# PSD5V.net
KiCad netlist of a schematic drawn in EAGLE
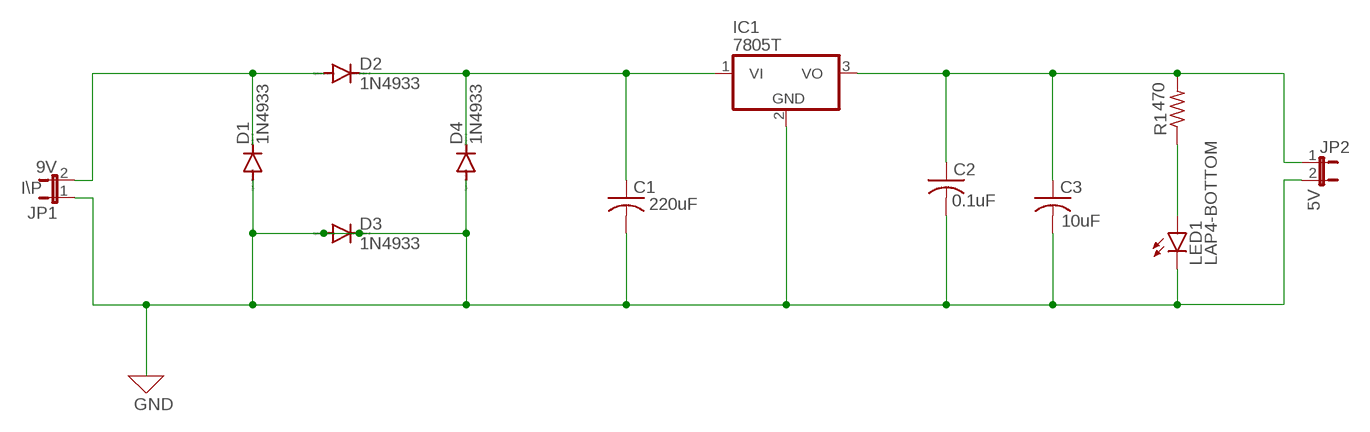
[diagram p0: schematic, sheet 1]

(export (version "E")
  (design (tool "Eeschema 10.0.6"))
  (components
    (comp (ref "C1")
      (value "C-US025-024X044")
      (footprint "eagle-import:C025-024X044")
      (libsource (lib "eagle-import") (part "C-US025-024X044"))
    )
    (comp (ref "C2")
      (value "C-US025-024X044")
      (footprint "eagle-import:C025-024X044")
      (libsource (lib "eagle-import") (part "C-US025-024X044"))
    )
    (comp (ref "C3")
      (value "C-US025-024X044")
      (footprint "eagle-import:C025-024X044")
      (libsource (lib "eagle-import") (part "C-US025-024X044"))
    )
    (comp (ref "D1")
      (value "1N4933")
      (footprint "eagle-import:DO41-10")
      (libsource (lib "eagle-import") (part "1N4933"))
    )
    (comp (ref "D2")
      (value "1N4933")
      (footprint "eagle-import:DO41-10")
      (libsource (lib "eagle-import") (part "1N4933"))
    )
    (comp (ref "D3")
      (value "1N4933")
      (footprint "eagle-import:DO41-10")
      (libsource (lib "eagle-import") (part "1N4933"))
    )
    (comp (ref "D4")
      (value "1N4933")
      (footprint "eagle-import:DO41-10")
      (libsource (lib "eagle-import") (part "1N4933"))
    )
    (comp (ref "IC1")
      (value "7805T")
      (footprint "eagle-import:TO220H")
      (libsource (lib "eagle-import") (part "78T05"))
    )
    (comp (ref "JP1")
      (value "JP1E")
      (footprint "eagle-import:JP1")
      (libsource (lib "eagle-import") (part "JP1E"))
    )
    (comp (ref "JP2")
      (value "JP1E")
      (footprint "eagle-import:JP1")
      (libsource (lib "eagle-import") (part "JP1E"))
    )
    (comp (ref "LED1")
      (value "LAP4-BOTTOM")
      (footprint "eagle-import:P47F-BOTTOM")
      (libsource (lib "eagle-import") (part "P4-BOTTOMLA"))
    )
    (comp (ref "R1")
      (value "R-US_0204/7")
      (footprint "eagle-import:0204_7")
      (libsource (lib "eagle-import") (part "R-US_0204/7"))
    )
  )
  (nets
    (net (code "1") (name "GND") (class "Default")
      (node (ref "C1") (pin "2") (pinfunction "2_2") (pintype "passive"))
      (node (ref "C2") (pin "2") (pinfunction "2_2") (pintype "passive"))
      (node (ref "C3") (pin "2") (pinfunction "2_2") (pintype "passive"))
      (node (ref "D1") (pin "A") (pinfunction "A_A") (pintype "passive"))
      (node (ref "D3") (pin "A") (pinfunction "A_A") (pintype "passive"))
      (node (ref "D3") (pin "C") (pinfunction "C_C") (pintype "passive"))
      (node (ref "D4") (pin "A") (pinfunction "A_A") (pintype "passive"))
      (node (ref "IC1") (pin "2") (pinfunction "GND_2") (pintype "passive"))
      (node (ref "JP1") (pin "1") (pinfunction "1_1") (pintype "passive"))
      (node (ref "JP2") (pin "2") (pinfunction "2_2") (pintype "passive"))
      (node (ref "LED1") (pin "C") (pinfunction "C_C") (pintype "passive"))
    )
    (net (code "2") (name "Net-(D1-PadC)") (class "Default")
      (node (ref "D1") (pin "C") (pinfunction "C_C") (pintype "passive"))
      (node (ref "D2") (pin "A") (pinfunction "A_A") (pintype "passive"))
      (node (ref "JP1") (pin "2") (pinfunction "2_2") (pintype "passive"))
    )
    (net (code "3") (name "Net-(IC1-VI)") (class "Default")
      (node (ref "C1") (pin "1") (pinfunction "1_1") (pintype "passive"))
      (node (ref "D2") (pin "C") (pinfunction "C_C") (pintype "passive"))
      (node (ref "D4") (pin "C") (pinfunction "C_C") (pintype "passive"))
      (node (ref "IC1") (pin "1") (pinfunction "VI_1") (pintype "input"))
    )
    (net (code "4") (name "Net-(IC1-VO)") (class "Default")
      (node (ref "C2") (pin "1") (pinfunction "1_1") (pintype "passive"))
      (node (ref "C3") (pin "1") (pinfunction "1_1") (pintype "passive"))
      (node (ref "IC1") (pin "3") (pinfunction "VO_3") (pintype "passive"))
      (node (ref "JP2") (pin "1") (pinfunction "1_1") (pintype "passive"))
      (node (ref "R1") (pin "2") (pinfunction "2_2") (pintype "passive"))
    )
    (net (code "5") (name "Net-(LED1-PadA)") (class "Default")
      (node (ref "LED1") (pin "A") (pinfunction "A_A") (pintype "passive"))
      (node (ref "R1") (pin "1") (pinfunction "1_1") (pintype "passive"))
    )
  )
)
